# untitled.net
KiCad netlist of a schematic drawn in EAGLE
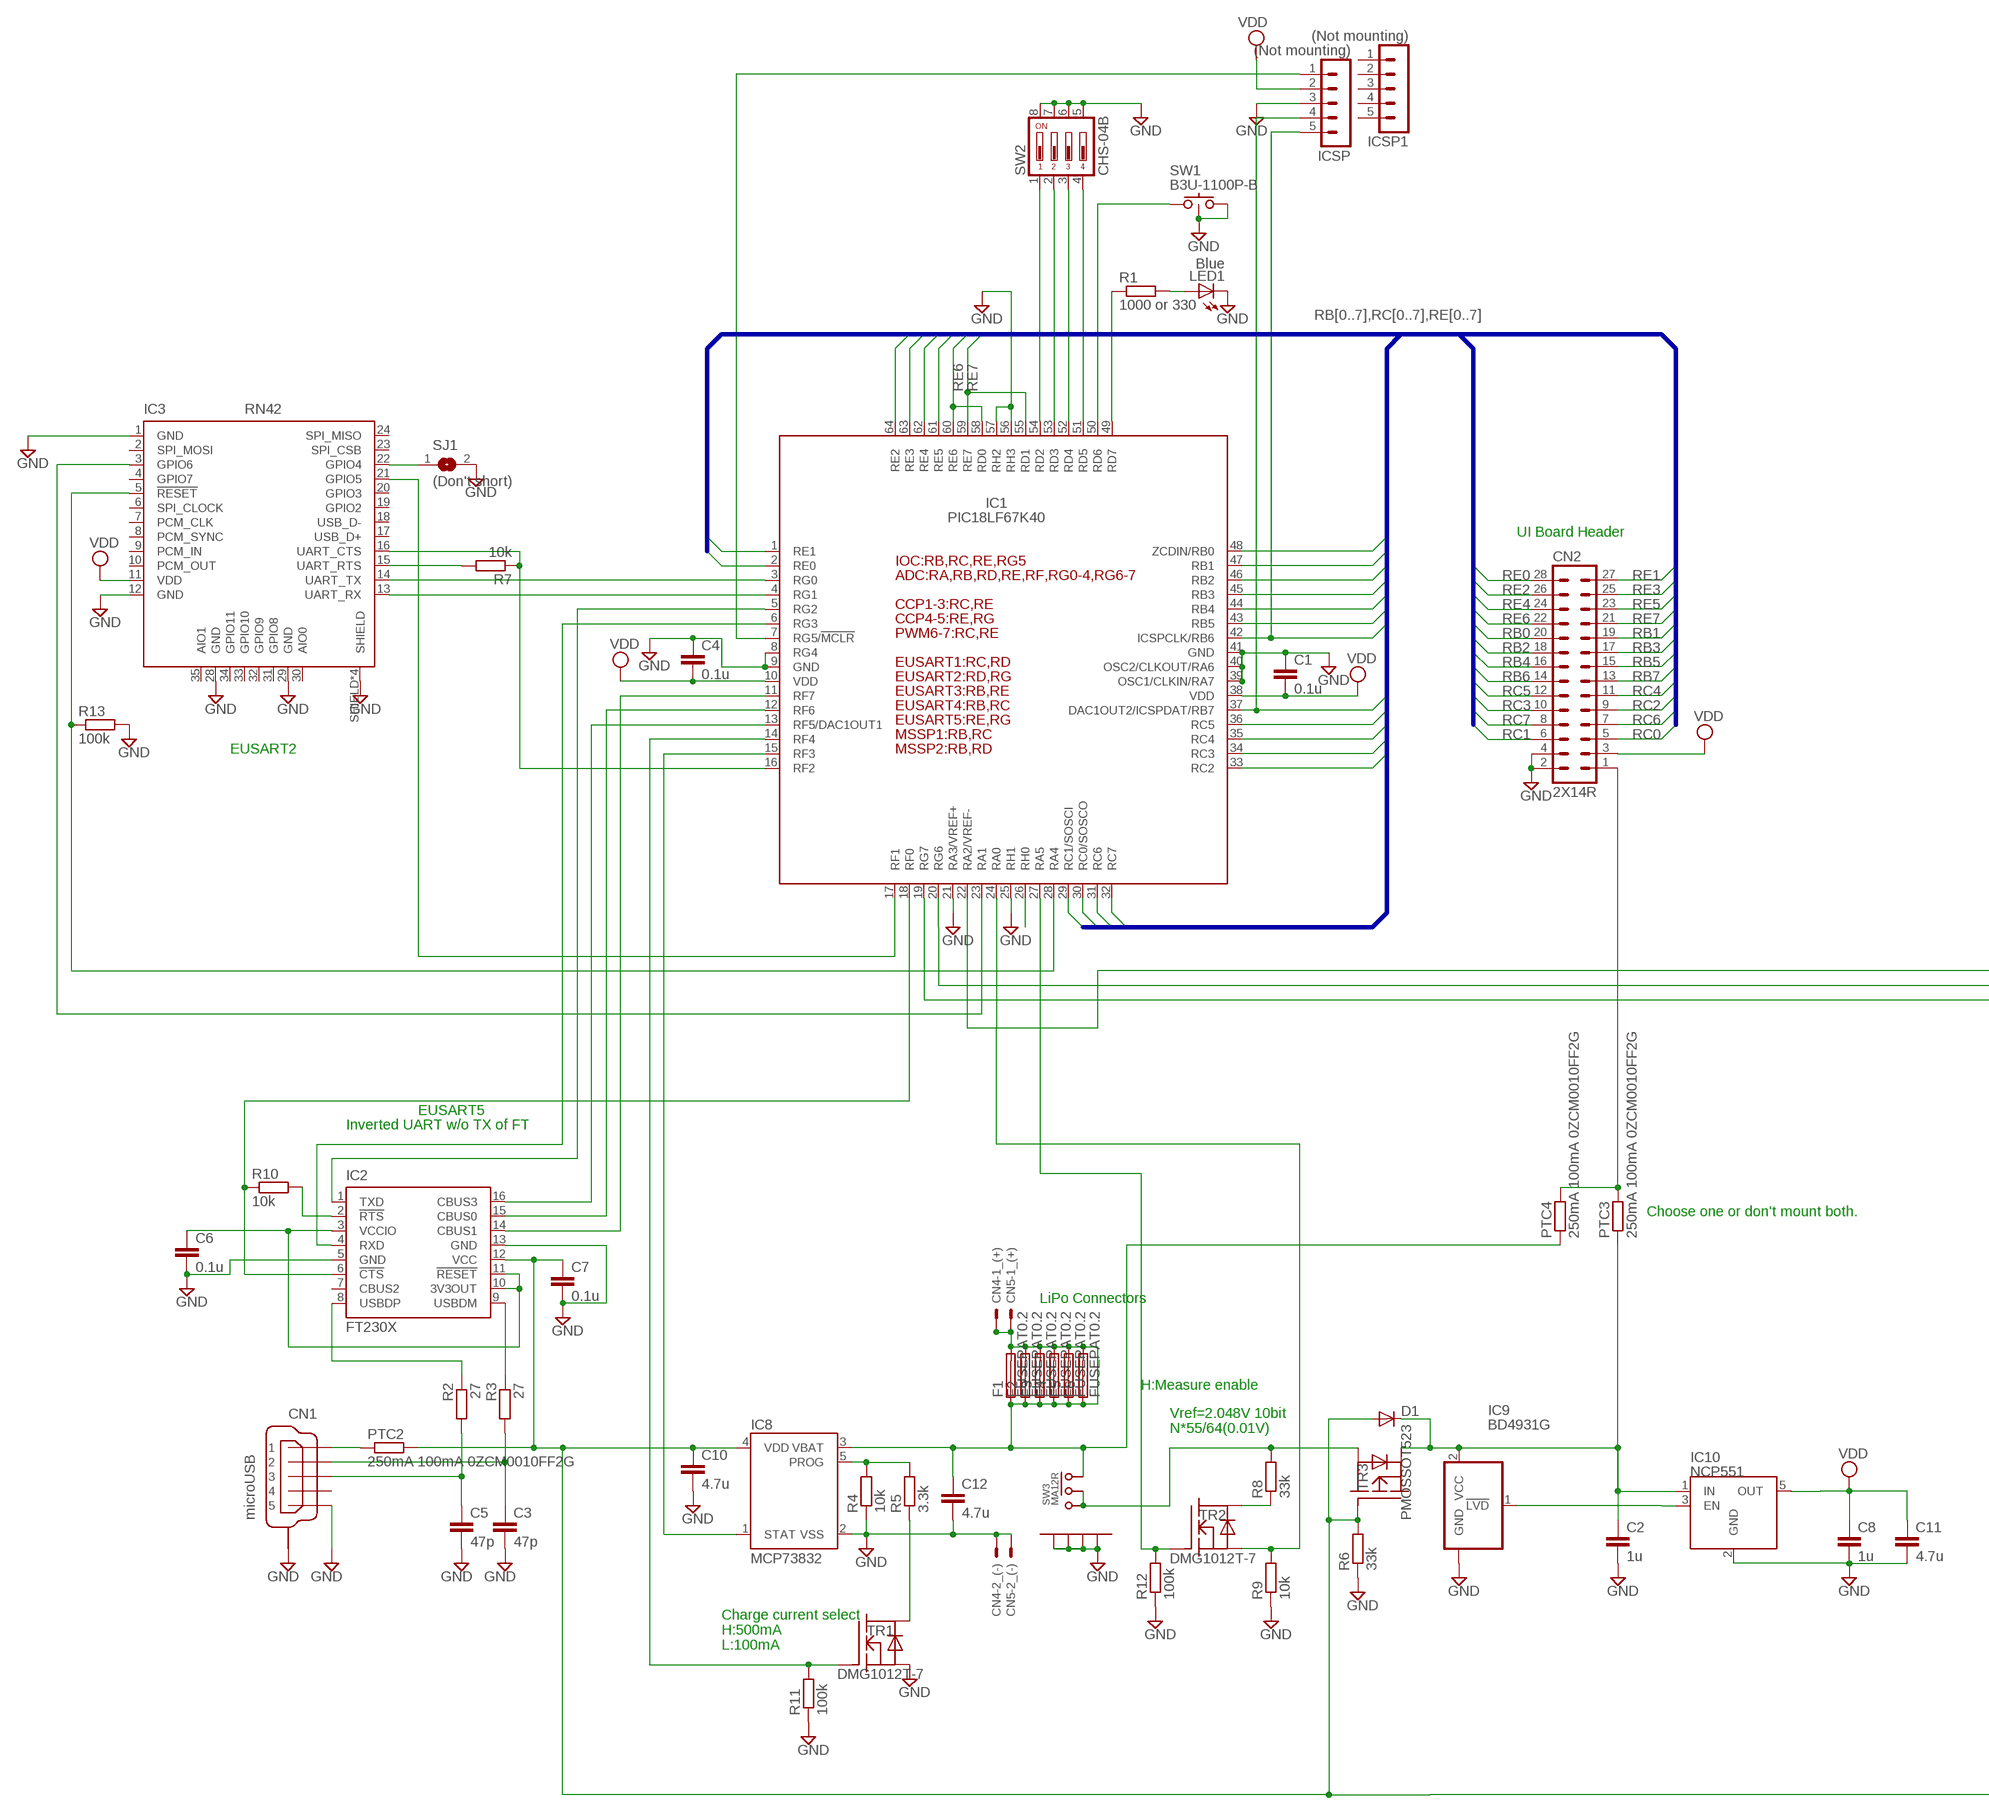
[diagram p0: schematic, sheet 1, part 1 of 2]
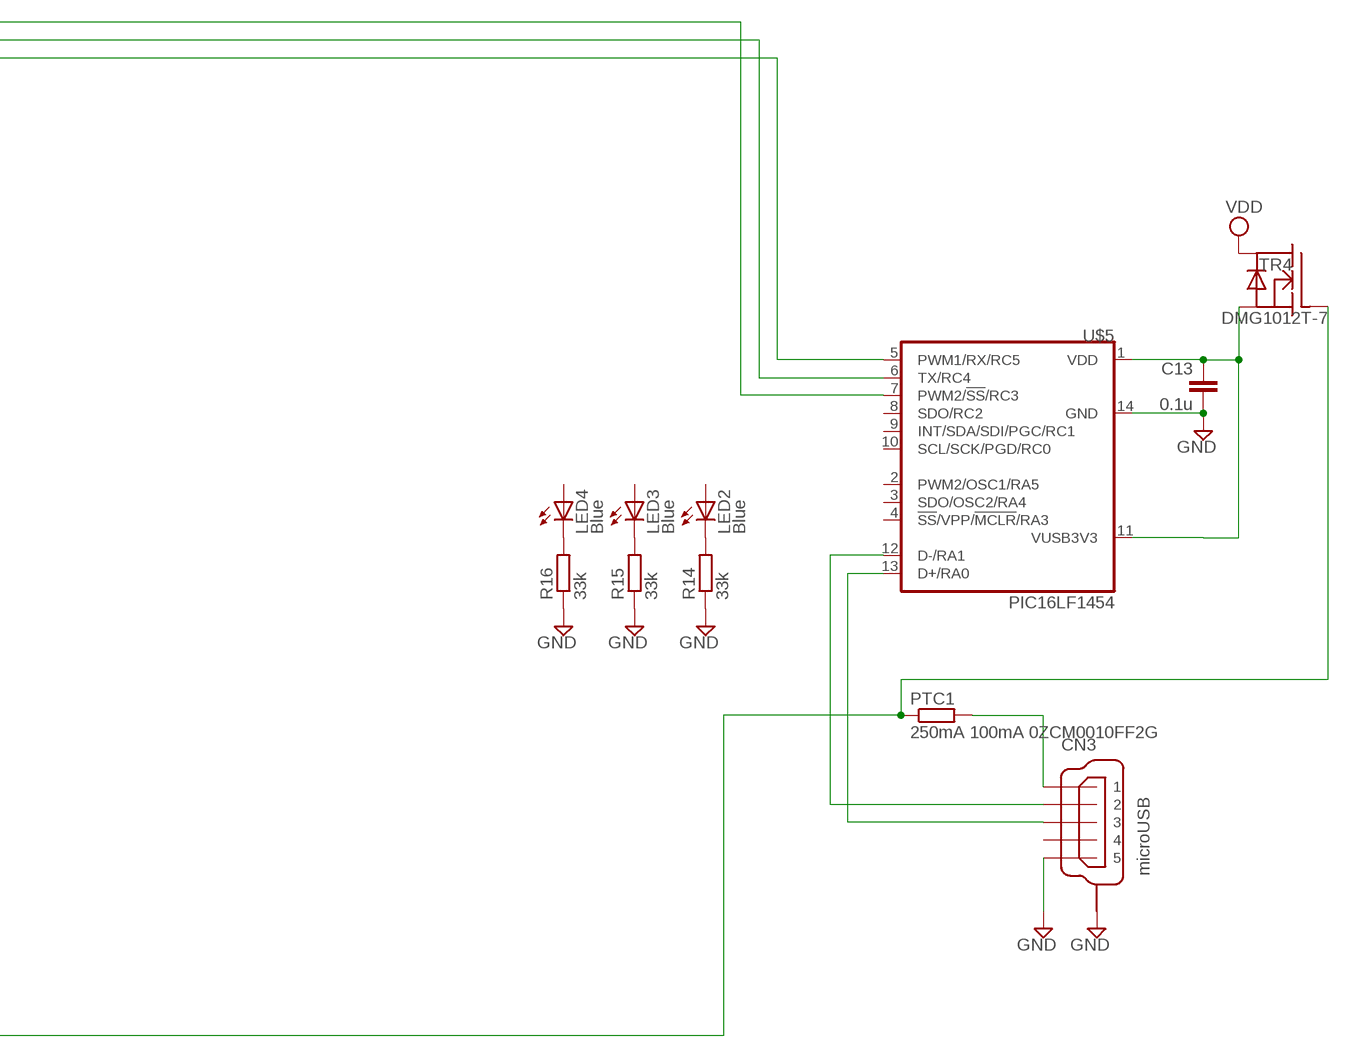
[diagram p1: schematic, sheet 1, part 2 of 2]

(export (version "E")
  (design (tool "Eeschema 10.0.6"))
  (components
    (comp (ref "C1")
      (value "0.1u")
      (footprint "eagle-import:C0402-SS")
      (libsource (lib "eagle-import") (part "C-EUC0402-SS"))
    )
    (comp (ref "C2")
      (value "1u")
      (footprint "eagle-import:C0805")
      (libsource (lib "eagle-import") (part "C-EUC0805"))
    )
    (comp (ref "C3")
      (value "47p")
      (footprint "eagle-import:C0402-SS")
      (libsource (lib "eagle-import") (part "C-EUC0402-SS"))
    )
    (comp (ref "C4")
      (value "0.1u")
      (footprint "eagle-import:C0402-SS")
      (libsource (lib "eagle-import") (part "C-EUC0402-SS"))
    )
    (comp (ref "C5")
      (value "47p")
      (footprint "eagle-import:C0402-SS")
      (libsource (lib "eagle-import") (part "C-EUC0402-SS"))
    )
    (comp (ref "C6")
      (value "0.1u")
      (footprint "eagle-import:C0402-SS")
      (libsource (lib "eagle-import") (part "C-EUC0402-SS"))
    )
    (comp (ref "C7")
      (value "0.1u")
      (footprint "eagle-import:C0402-SS")
      (libsource (lib "eagle-import") (part "C-EUC0402-SS"))
    )
    (comp (ref "C8")
      (value "1u")
      (footprint "eagle-import:C0805")
      (libsource (lib "eagle-import") (part "C-EUC0805"))
    )
    (comp (ref "C10")
      (value "4.7u")
      (footprint "eagle-import:C0805")
      (libsource (lib "eagle-import") (part "C-EUC0805"))
    )
    (comp (ref "C11")
      (value "4.7u")
      (footprint "eagle-import:C0805")
      (libsource (lib "eagle-import") (part "C-EUC0805"))
    )
    (comp (ref "C12")
      (value "4.7u")
      (footprint "eagle-import:C0805")
      (libsource (lib "eagle-import") (part "C-EUC0805"))
    )
    (comp (ref "C13")
      (value "0.1u")
      (footprint "eagle-import:C0402-SS")
      (libsource (lib "eagle-import") (part "C-EUC0402-SS"))
    )
    (comp (ref "CN1")
      (value "microUSB")
      (footprint "eagle-import:10118194-0001LF")
      (libsource (lib "eagle-import") (part "MICROUSB(10118194-0001LF)"))
    )
    (comp (ref "CN2")
      (value "2X14R")
      (footprint "eagle-import:2MM_14X2_R")
      (libsource (lib "eagle-import") (part "2X14R"))
    )
    (comp (ref "CN3")
      (value "microUSB")
      (footprint "eagle-import:10118194-0001LF")
      (libsource (lib "eagle-import") (part "MICROUSB(10118194-0001LF)"))
    )
    (comp (ref "CN4")
      (value "2P_(POWER)PH_S")
      (footprint "eagle-import:PH-2_S")
      (libsource (lib "eagle-import") (part "2P_(POWER)PH_S"))
    )
    (comp (ref "CN5")
      (value "2P_(POWER)PH_S")
      (footprint "eagle-import:PH-2_S")
      (libsource (lib "eagle-import") (part "2P_(POWER)PH_S"))
    )
    (comp (ref "D1")
      (value "DIODE-VMN2")
      (footprint "eagle-import:VMN2")
      (libsource (lib "eagle-import") (part "DIODE-VMN2"))
    )
    (comp (ref "F1")
      (value "FUSEPAT0.2")
      (footprint "eagle-import:FUSE_PAT1")
      (libsource (lib "eagle-import") (part "FUSEPAT0.2"))
    )
    (comp (ref "F2")
      (value "FUSEPAT0.2")
      (footprint "eagle-import:FUSE_PAT1")
      (libsource (lib "eagle-import") (part "FUSEPAT0.2"))
    )
    (comp (ref "F3")
      (value "FUSEPAT0.2")
      (footprint "eagle-import:FUSE_PAT1")
      (libsource (lib "eagle-import") (part "FUSEPAT0.2"))
    )
    (comp (ref "F4")
      (value "FUSEPAT0.2")
      (footprint "eagle-import:FUSE_PAT1")
      (libsource (lib "eagle-import") (part "FUSEPAT0.2"))
    )
    (comp (ref "F5")
      (value "FUSEPAT0.2")
      (footprint "eagle-import:FUSE_PAT1")
      (libsource (lib "eagle-import") (part "FUSEPAT0.2"))
    )
    (comp (ref "F6")
      (value "FUSEPAT0.2")
      (footprint "eagle-import:FUSE_PAT1")
      (libsource (lib "eagle-import") (part "FUSEPAT0.2"))
    )
    (comp (ref "IC1")
      (value "PIC18LF67K40")
      (footprint "eagle-import:TQFP64-10X10")
      (libsource (lib "eagle-import") (part "PIC18F67K40"))
    )
    (comp (ref "IC2")
      (value "FT230X")
      (footprint "eagle-import:SSOP16")
      (libsource (lib "eagle-import") (part "FT230XS"))
    )
    (comp (ref "IC3")
      (value "RN42")
      (footprint "eagle-import:RN-42")
      (libsource (lib "eagle-import") (part "RN-42"))
    )
    (comp (ref "IC8")
      (value "MCP73832")
      (footprint "eagle-import:SOT23-5L")
      (libsource (lib "eagle-import") (part "MCP73831"))
    )
    (comp (ref "IC9")
      (value "BD4931G")
      (footprint "eagle-import:SOT23-5L")
      (libsource (lib "eagle-import") (part "BD48XX"))
    )
    (comp (ref "IC10")
      (value "NCP551")
      (footprint "eagle-import:SOT23-5L")
      (libsource (lib "eagle-import") (part "NCP551"))
    )
    (comp (ref "ICSP")
      (value "(Not mounting)")
      (footprint "eagle-import:MA05-1")
      (libsource (lib "eagle-import") (part "MA05-1"))
    )
    (comp (ref "ICSP1")
      (value "(Not mounting)")
      (footprint "eagle-import:MA05-1")
      (libsource (lib "eagle-import") (part "MA05-1"))
    )
    (comp (ref "LED1")
      (value "Blue")
      (footprint "eagle-import:CHIP-LED1005")
      (libsource (lib "eagle-import") (part "LED1005"))
    )
    (comp (ref "LED2")
      (value "Blue")
      (footprint "eagle-import:CHIP-LED1606(SIDE)")
      (libsource (lib "eagle-import") (part "LEDCHIPLED_1606(SIDE)"))
    )
    (comp (ref "LED3")
      (value "Blue")
      (footprint "eagle-import:CHIP-LED1606(SIDE)")
      (libsource (lib "eagle-import") (part "LEDCHIPLED_1606(SIDE)"))
    )
    (comp (ref "LED4")
      (value "Blue")
      (footprint "eagle-import:CHIP-LED1606(SIDE)")
      (libsource (lib "eagle-import") (part "LEDCHIPLED_1606(SIDE)"))
    )
    (comp (ref "PTC1")
      (value "250mA 100mA 0ZCM0010FF2G")
      (footprint "eagle-import:R0603")
      (libsource (lib "eagle-import") (part "R-EU_R0603"))
    )
    (comp (ref "PTC2")
      (value "250mA 100mA 0ZCM0010FF2G")
      (footprint "eagle-import:R0603")
      (libsource (lib "eagle-import") (part "R-EU_R0603"))
    )
    (comp (ref "PTC3")
      (value "250mA 100mA 0ZCM0010FF2G")
      (footprint "eagle-import:R0603")
      (libsource (lib "eagle-import") (part "R-EU_R0603"))
    )
    (comp (ref "PTC4")
      (value "250mA 100mA 0ZCM0010FF2G")
      (footprint "eagle-import:R0603")
      (libsource (lib "eagle-import") (part "R-EU_R0603"))
    )
    (comp (ref "R1")
      (value "1000 or 330")
      (footprint "eagle-import:R0402-SS")
      (libsource (lib "eagle-import") (part "R-EU_R0402-SS"))
    )
    (comp (ref "R2")
      (value "27")
      (footprint "eagle-import:R0402-SS")
      (libsource (lib "eagle-import") (part "R-EU_R0402-SS"))
    )
    (comp (ref "R3")
      (value "27")
      (footprint "eagle-import:R0402-SS")
      (libsource (lib "eagle-import") (part "R-EU_R0402-SS"))
    )
    (comp (ref "R4")
      (value "10k")
      (footprint "eagle-import:R0402-SS")
      (libsource (lib "eagle-import") (part "R-EU_R0402-SS"))
    )
    (comp (ref "R5")
      (value "3.3k")
      (footprint "eagle-import:R0402-SS")
      (libsource (lib "eagle-import") (part "R-EU_R0402-SS"))
    )
    (comp (ref "R6")
      (value "33k")
      (footprint "eagle-import:R0402-SS")
      (libsource (lib "eagle-import") (part "R-EU_R0402-SS"))
    )
    (comp (ref "R7")
      (value "10k")
      (footprint "eagle-import:R0402-SS")
      (libsource (lib "eagle-import") (part "R-EU_R0402-SS"))
    )
    (comp (ref "R8")
      (value "33k")
      (footprint "eagle-import:R0402-SS")
      (libsource (lib "eagle-import") (part "R-EU_R0402-SS"))
    )
    (comp (ref "R9")
      (value "10k")
      (footprint "eagle-import:R0402-SS")
      (libsource (lib "eagle-import") (part "R-EU_R0402-SS"))
    )
    (comp (ref "R10")
      (value "10k")
      (footprint "eagle-import:R0402-SS")
      (libsource (lib "eagle-import") (part "R-EU_R0402-SS"))
    )
    (comp (ref "R11")
      (value "100k")
      (footprint "eagle-import:R0402-SS")
      (libsource (lib "eagle-import") (part "R-EU_R0402-SS"))
    )
    (comp (ref "R12")
      (value "100k")
      (footprint "eagle-import:R0402-SS")
      (libsource (lib "eagle-import") (part "R-EU_R0402-SS"))
    )
    (comp (ref "R13")
      (value "100k")
      (footprint "eagle-import:R0402-SS")
      (libsource (lib "eagle-import") (part "R-EU_R0402-SS"))
    )
    (comp (ref "R14")
      (value "33k")
      (footprint "eagle-import:R0402-SS")
      (libsource (lib "eagle-import") (part "R-EU_R0402-SS"))
    )
    (comp (ref "R15")
      (value "33k")
      (footprint "eagle-import:R0402-SS")
      (libsource (lib "eagle-import") (part "R-EU_R0402-SS"))
    )
    (comp (ref "R16")
      (value "33k")
      (footprint "eagle-import:R0402-SS")
      (libsource (lib "eagle-import") (part "R-EU_R0402-SS"))
    )
    (comp (ref "SJ1")
      (value "(Don't short)")
      (footprint "eagle-import:SJ")
      (libsource (lib "eagle-import") (part "SJ"))
    )
    (comp (ref "SW1")
      (value "B3U-1100P-B")
      (footprint "eagle-import:B3U-1100P-B")
      (libsource (lib "eagle-import") (part "SW_WITH_EARTH(B3U-1100P)"))
    )
    (comp (ref "SW2")
      (value "CHS-04B")
      (footprint "eagle-import:CHS-04B")
      (libsource (lib "eagle-import") (part "CHS-04B"))
    )
    (comp (ref "SW3")
      (value "MA12R")
      (footprint "eagle-import:MA12R")
      (libsource (lib "eagle-import") (part "MA12R"))
    )
    (comp (ref "TR1")
      (value "DMG1012T-7")
      (footprint "eagle-import:SOT523")
      (libsource (lib "eagle-import") (part "NMOSSOT523"))
    )
    (comp (ref "TR2")
      (value "DMG1012T-7")
      (footprint "eagle-import:SOT523")
      (libsource (lib "eagle-import") (part "NMOSSOT523"))
    )
    (comp (ref "TR3")
      (value "PMOSSOT523")
      (footprint "eagle-import:SOT523")
      (libsource (lib "eagle-import") (part "PMOSSOT523"))
    )
    (comp (ref "TR4")
      (value "DMG1012T-7")
      (footprint "eagle-import:SOT523")
      (libsource (lib "eagle-import") (part "NMOSSOT523"))
    )
    (comp (ref "U$5")
      (value "PIC16LF1454")
      (footprint "eagle-import:TSSOP14")
      (libsource (lib "eagle-import") (part "PIC16F1454"))
    )
  )
  (nets
    (net (code "1") (name "/RB0") (class "Default")
      (node (ref "CN2") (pin "20") (pinfunction "20_20") (pintype "passive"))
      (node (ref "IC1") (pin "48") (pinfunction "ZCDIN/RB0_48") (pintype "bidirectional"))
    )
    (net (code "2") (name "/RB1") (class "Default")
      (node (ref "CN2") (pin "19") (pinfunction "19_19") (pintype "passive"))
      (node (ref "IC1") (pin "47") (pinfunction "RB1_47") (pintype "bidirectional"))
    )
    (net (code "3") (name "/RB2") (class "Default")
      (node (ref "CN2") (pin "18") (pinfunction "18_18") (pintype "passive"))
      (node (ref "IC1") (pin "46") (pinfunction "RB2_46") (pintype "bidirectional"))
    )
    (net (code "4") (name "/RB3") (class "Default")
      (node (ref "CN2") (pin "17") (pinfunction "17_17") (pintype "passive"))
      (node (ref "IC1") (pin "45") (pinfunction "RB3_45") (pintype "bidirectional"))
    )
    (net (code "5") (name "/RB4") (class "Default")
      (node (ref "CN2") (pin "16") (pinfunction "16_16") (pintype "passive"))
      (node (ref "IC1") (pin "44") (pinfunction "RB4_44") (pintype "bidirectional"))
    )
    (net (code "6") (name "/RB5") (class "Default")
      (node (ref "CN2") (pin "15") (pinfunction "15_15") (pintype "passive"))
      (node (ref "IC1") (pin "43") (pinfunction "RB5_43") (pintype "bidirectional"))
    )
    (net (code "7") (name "/RB6") (class "Default")
      (node (ref "CN2") (pin "14") (pinfunction "14_14") (pintype "passive"))
      (node (ref "IC1") (pin "42") (pinfunction "ICSPCLK/RB6_42") (pintype "bidirectional"))
      (node (ref "ICSP") (pin "5") (pinfunction "5_5") (pintype "passive"))
    )
    (net (code "8") (name "/RB7") (class "Default")
      (node (ref "CN2") (pin "13") (pinfunction "13_13") (pintype "passive"))
      (node (ref "IC1") (pin "37") (pinfunction "DAC1OUT2/ICSPDAT/RB7_37") (pintype "bidirectional"))
      (node (ref "ICSP") (pin "4") (pinfunction "4_4") (pintype "passive"))
    )
    (net (code "9") (name "/RC0") (class "Default")
      (node (ref "CN2") (pin "5") (pinfunction "5_5") (pintype "passive"))
      (node (ref "IC1") (pin "30") (pinfunction "RC0/SOSCO_30") (pintype "bidirectional"))
    )
    (net (code "10") (name "/RC1") (class "Default")
      (node (ref "CN2") (pin "6") (pinfunction "6_6") (pintype "passive"))
      (node (ref "IC1") (pin "29") (pinfunction "RC1/SOSCI_29") (pintype "bidirectional"))
    )
    (net (code "11") (name "/RC2") (class "Default")
      (node (ref "CN2") (pin "9") (pinfunction "9_9") (pintype "passive"))
      (node (ref "IC1") (pin "33") (pinfunction "RC2_33") (pintype "bidirectional"))
    )
    (net (code "12") (name "/RC3") (class "Default")
      (node (ref "CN2") (pin "10") (pinfunction "10_10") (pintype "passive"))
      (node (ref "IC1") (pin "34") (pinfunction "RC3_34") (pintype "bidirectional"))
    )
    (net (code "13") (name "/RC4") (class "Default")
      (node (ref "CN2") (pin "11") (pinfunction "11_11") (pintype "passive"))
      (node (ref "IC1") (pin "35") (pinfunction "RC4_35") (pintype "bidirectional"))
    )
    (net (code "14") (name "/RC5") (class "Default")
      (node (ref "CN2") (pin "12") (pinfunction "12_12") (pintype "passive"))
      (node (ref "IC1") (pin "36") (pinfunction "RC5_36") (pintype "bidirectional"))
    )
    (net (code "15") (name "/RC6") (class "Default")
      (node (ref "CN2") (pin "7") (pinfunction "7_7") (pintype "passive"))
      (node (ref "IC1") (pin "31") (pinfunction "RC6_31") (pintype "bidirectional"))
    )
    (net (code "16") (name "/RC7") (class "Default")
      (node (ref "CN2") (pin "8") (pinfunction "8_8") (pintype "passive"))
      (node (ref "IC1") (pin "32") (pinfunction "RC7_32") (pintype "bidirectional"))
    )
    (net (code "17") (name "/RE0") (class "Default")
      (node (ref "CN2") (pin "28") (pinfunction "28_28") (pintype "passive"))
      (node (ref "IC1") (pin "2") (pinfunction "RE0_2") (pintype "bidirectional"))
    )
    (net (code "18") (name "/RE1") (class "Default")
      (node (ref "CN2") (pin "27") (pinfunction "27_27") (pintype "passive"))
      (node (ref "IC1") (pin "1") (pinfunction "RE1_1") (pintype "bidirectional"))
    )
    (net (code "19") (name "/RE2") (class "Default")
      (node (ref "CN2") (pin "26") (pinfunction "26_26") (pintype "passive"))
      (node (ref "IC1") (pin "64") (pinfunction "RE2_64") (pintype "bidirectional"))
    )
    (net (code "20") (name "/RE3") (class "Default")
      (node (ref "CN2") (pin "25") (pinfunction "25_25") (pintype "passive"))
      (node (ref "IC1") (pin "63") (pinfunction "RE3_63") (pintype "bidirectional"))
    )
    (net (code "21") (name "/RE4") (class "Default")
      (node (ref "CN2") (pin "24") (pinfunction "24_24") (pintype "passive"))
      (node (ref "IC1") (pin "62") (pinfunction "RE4_62") (pintype "bidirectional"))
    )
    (net (code "22") (name "/RE5") (class "Default")
      (node (ref "CN2") (pin "23") (pinfunction "23_23") (pintype "passive"))
      (node (ref "IC1") (pin "61") (pinfunction "RE5_61") (pintype "bidirectional"))
    )
    (net (code "23") (name "/RE6") (class "Default")
      (node (ref "CN2") (pin "22") (pinfunction "22_22") (pintype "passive"))
      (node (ref "IC1") (pin "58") (pinfunction "RD0_58") (pintype "bidirectional"))
      (node (ref "IC1") (pin "60") (pinfunction "RE6_60") (pintype "bidirectional"))
    )
    (net (code "24") (name "/RE7") (class "Default")
      (node (ref "CN2") (pin "21") (pinfunction "21_21") (pintype "passive"))
      (node (ref "IC1") (pin "55") (pinfunction "RD1_55") (pintype "bidirectional"))
      (node (ref "IC1") (pin "59") (pinfunction "RE7_59") (pintype "bidirectional"))
    )
    (net (code "26") (name "GND") (class "Default")
      (node (ref "C1") (pin "1") (pinfunction "1_1") (pintype "passive"))
      (node (ref "C10") (pin "2") (pinfunction "2_2") (pintype "passive"))
      (node (ref "C11") (pin "2") (pinfunction "2_2") (pintype "passive"))
      (node (ref "C12") (pin "2") (pinfunction "2_2") (pintype "passive"))
      (node (ref "C13") (pin "2") (pinfunction "2_2") (pintype "passive"))
      (node (ref "C2") (pin "2") (pinfunction "2_2") (pintype "passive"))
      (node (ref "C3") (pin "2") (pinfunction "2_2") (pintype "passive"))
      (node (ref "C4") (pin "1") (pinfunction "1_1") (pintype "passive"))
      (node (ref "C5") (pin "2") (pinfunction "2_2") (pintype "passive"))
      (node (ref "C6") (pin "2") (pinfunction "2_2") (pintype "passive"))
      (node (ref "C7") (pin "2") (pinfunction "2_2") (pintype "passive"))
      (node (ref "C8") (pin "2") (pinfunction "2_2") (pintype "passive"))
      (node (ref "CN1") (pin "P$5") (pinfunction "5_P$5") (pintype "passive"))
      (node (ref "CN1") (pin "P$6") (pinfunction "S_P$6") (pintype "passive"))
      (node (ref "CN1") (pin "P$7") (pinfunction "S_P$7") (pintype "passive"))
      (node (ref "CN1") (pin "S1") (pinfunction "S_S1") (pintype "passive"))
      (node (ref "CN1") (pin "S10") (pinfunction "S_S10") (pintype "passive"))
      (node (ref "CN1") (pin "S2") (pinfunction "S_S2") (pintype "passive"))
      (node (ref "CN1") (pin "S3") (pinfunction "S_S3") (pintype "passive"))
      (node (ref "CN1") (pin "S4") (pinfunction "S_S4") (pintype "passive"))
      (node (ref "CN1") (pin "S5") (pinfunction "S_S5") (pintype "passive"))
      (node (ref "CN1") (pin "S6") (pinfunction "S_S6") (pintype "passive"))
      (node (ref "CN1") (pin "S7") (pinfunction "S_S7") (pintype "passive"))
      (node (ref "CN1") (pin "S8") (pinfunction "S_S8") (pintype "passive"))
      (node (ref "CN1") (pin "S9") (pinfunction "S_S9") (pintype "passive"))
      (node (ref "CN2") (pin "2") (pinfunction "2_2") (pintype "passive"))
      (node (ref "CN2") (pin "4") (pinfunction "4_4") (pintype "passive"))
      (node (ref "CN3") (pin "P$5") (pinfunction "5_P$5") (pintype "passive"))
      (node (ref "CN3") (pin "P$6") (pinfunction "S_P$6") (pintype "passive"))
      (node (ref "CN3") (pin "P$7") (pinfunction "S_P$7") (pintype "passive"))
      (node (ref "CN3") (pin "S1") (pinfunction "S_S1") (pintype "passive"))
      (node (ref "CN3") (pin "S10") (pinfunction "S_S10") (pintype "passive"))
      (node (ref "CN3") (pin "S2") (pinfunction "S_S2") (pintype "passive"))
      (node (ref "CN3") (pin "S3") (pinfunction "S_S3") (pintype "passive"))
      (node (ref "CN3") (pin "S4") (pinfunction "S_S4") (pintype "passive"))
      (node (ref "CN3") (pin "S5") (pinfunction "S_S5") (pintype "passive"))
      (node (ref "CN3") (pin "S6") (pinfunction "S_S6") (pintype "passive"))
      (node (ref "CN3") (pin "S7") (pinfunction "S_S7") (pintype "passive"))
      (node (ref "CN3") (pin "S8") (pinfunction "S_S8") (pintype "passive"))
      (node (ref "CN3") (pin "S9") (pinfunction "S_S9") (pintype "passive"))
      (node (ref "CN4") (pin "2") (pinfunction "S_2") (pintype "passive"))
      (node (ref "CN5") (pin "2") (pinfunction "S_2") (pintype "passive"))
      (node (ref "IC1") (pin "21") (pinfunction "RA3/VREF+_21") (pintype "bidirectional"))
      (node (ref "IC1") (pin "25") (pinfunction "RH1_25") (pintype "bidirectional"))
      (node (ref "IC1") (pin "39") (pinfunction "OSC1/CLKIN/RA7_39") (pintype "bidirectional"))
      (node (ref "IC1") (pin "40") (pinfunction "OSC2/CLKOUT/RA6_40") (pintype "bidirectional"))
      (node (ref "IC1") (pin "41") (pinfunction "GND_41") (pintype "power_in"))
      (node (ref "IC1") (pin "56") (pinfunction "RH3_56") (pintype "bidirectional"))
      (node (ref "IC1") (pin "57") (pinfunction "RH2_57") (pintype "bidirectional"))
      (node (ref "IC1") (pin "8") (pinfunction "RG4_8") (pintype "bidirectional"))
      (node (ref "IC1") (pin "9") (pinfunction "GND_9") (pintype "power_in"))
      (node (ref "IC10") (pin "2") (pinfunction "GND_2") (pintype "power_in"))
      (node (ref "IC2") (pin "13") (pinfunction "GND_13") (pintype "power_in"))
      (node (ref "IC2") (pin "5") (pinfunction "GND_5") (pintype "power_in"))
      (node (ref "IC3") (pin "1") (pinfunction "GND_1") (pintype "bidirectional"))
      (node (ref "IC3") (pin "12") (pinfunction "GND_12") (pintype "bidirectional"))
      (node (ref "IC3") (pin "28") (pinfunction "GND_28") (pintype "bidirectional"))
      (node (ref "IC3") (pin "29") (pinfunction "GND_29") (pintype "bidirectional"))
      (node (ref "IC3") (pin "SHIELD") (pinfunction "SHIELD_SHIELD") (pintype "bidirectional"))
      (node (ref "IC3") (pin "SHIELD@1") (pinfunction "SHIELD_SHIELD@1") (pintype "bidirectional"))
      (node (ref "IC3") (pin "SHIELD@2") (pinfunction "SHIELD_SHIELD@2") (pintype "bidirectional"))
      (node (ref "IC3") (pin "SHIELD@3") (pinfunction "SHIELD_SHIELD@3") (pintype "bidirectional"))
      (node (ref "IC8") (pin "2") (pinfunction "VSS_2") (pintype "power_in"))
      (node (ref "IC9") (pin "3") (pinfunction "GND_3") (pintype "power_in"))
      (node (ref "ICSP") (pin "3") (pinfunction "3_3") (pintype "passive"))
      (node (ref "LED1") (pin "C") (pinfunction "C_C") (pintype "passive"))
      (node (ref "R11") (pin "1") (pinfunction "1_1") (pintype "passive"))
      (node (ref "R12") (pin "1") (pinfunction "1_1") (pintype "passive"))
      (node (ref "R13") (pin "2") (pinfunction "2_2") (pintype "passive"))
      (node (ref "R14") (pin "1") (pinfunction "1_1") (pintype "passive"))
      (node (ref "R15") (pin "1") (pinfunction "1_1") (pintype "passive"))
      (node (ref "R16") (pin "1") (pinfunction "1_1") (pintype "passive"))
      (node (ref "R4") (pin "1") (pinfunction "1_1") (pintype "passive"))
      (node (ref "R6") (pin "1") (pinfunction "1_1") (pintype "passive"))
      (node (ref "R9") (pin "1") (pinfunction "1_1") (pintype "passive"))
      (node (ref "SJ1") (pin "2") (pinfunction "2_2") (pintype "passive"))
      (node (ref "SW1") (pin "P$2") (pinfunction "P$2_P$2") (pintype "passive"))
      (node (ref "SW1") (pin "P$3") (pinfunction "P$3_P$3") (pintype "passive"))
      (node (ref "SW2") (pin "5") (pinfunction "5_5") (pintype "passive"))
      (node (ref "SW2") (pin "6") (pinfunction "6_6") (pintype "passive"))
      (node (ref "SW2") (pin "7") (pinfunction "7_7") (pintype "passive"))
      (node (ref "SW2") (pin "8") (pinfunction "8_8") (pintype "passive"))
      (node (ref "SW3") (pin "P$4") (pinfunction "P$1_P$4") (pintype "bidirectional"))
      (node (ref "SW3") (pin "P$5") (pinfunction "P$2_P$5") (pintype "bidirectional"))
      (node (ref "SW3") (pin "P$6") (pinfunction "P$3_P$6") (pintype "bidirectional"))
      (node (ref "SW3") (pin "P$7") (pinfunction "P$4_P$7") (pintype "bidirectional"))
      (node (ref "TR1") (pin "2") (pinfunction "S_2") (pintype "bidirectional"))
      (node (ref "U$5") (pin "14") (pinfunction "GND_14") (pintype "power_in"))
    )
    (net (code "27") (name "Net-(CN1-1)") (class "Default")
      (node (ref "CN1") (pin "P$1") (pinfunction "1_P$1") (pintype "passive"))
      (node (ref "PTC2") (pin "1") (pinfunction "1_1") (pintype "passive"))
    )
    (net (code "28") (name "Net-(CN1-2)") (class "Default")
      (node (ref "C3") (pin "1") (pinfunction "1_1") (pintype "passive"))
      (node (ref "CN1") (pin "P$2") (pinfunction "2_P$2") (pintype "passive"))
      (node (ref "R3") (pin "2") (pinfunction "2_2") (pintype "passive"))
    )
    (net (code "29") (name "Net-(CN1-3)") (class "Default")
      (node (ref "C5") (pin "1") (pinfunction "1_1") (pintype "passive"))
      (node (ref "CN1") (pin "P$3") (pinfunction "3_P$3") (pintype "passive"))
      (node (ref "R2") (pin "2") (pinfunction "2_2") (pintype "passive"))
    )
    (net (code "30") (name "Net-(CN2-Pad1)") (class "Default")
      (node (ref "CN2") (pin "1") (pinfunction "1_1") (pintype "passive"))
      (node (ref "PTC3") (pin "2") (pinfunction "2_2") (pintype "passive"))
      (node (ref "PTC4") (pin "2") (pinfunction "2_2") (pintype "passive"))
    )
    (net (code "31") (name "Net-(CN3-1)") (class "Default")
      (node (ref "CN3") (pin "P$1") (pinfunction "1_P$1") (pintype "passive"))
      (node (ref "PTC1") (pin "2") (pinfunction "2_2") (pintype "passive"))
    )
    (net (code "32") (name "Net-(CN3-2)") (class "Default")
      (node (ref "CN3") (pin "P$2") (pinfunction "2_P$2") (pintype "passive"))
      (node (ref "U$5") (pin "12") (pinfunction "D-/RA1_12") (pintype "bidirectional"))
    )
    (net (code "33") (name "Net-(CN3-3)") (class "Default")
      (node (ref "CN3") (pin "P$3") (pinfunction "3_P$3") (pintype "passive"))
      (node (ref "U$5") (pin "13") (pinfunction "D+/RA0_13") (pintype "bidirectional"))
    )
    (net (code "34") (name "Net-(CN4A-S)") (class "Default")
      (node (ref "C12") (pin "1") (pinfunction "1_1") (pintype "passive"))
      (node (ref "CN4") (pin "1") (pinfunction "S_1") (pintype "passive"))
      (node (ref "CN5") (pin "1") (pinfunction "S_1") (pintype "passive"))
      (node (ref "F1") (pin "P$1") (pinfunction "1_P$1") (pintype "passive"))
      (node (ref "F1") (pin "P$2") (pinfunction "2_P$2") (pintype "passive"))
      (node (ref "F2") (pin "P$1") (pinfunction "1_P$1") (pintype "passive"))
      (node (ref "F2") (pin "P$2") (pinfunction "2_P$2") (pintype "passive"))
      (node (ref "F3") (pin "P$1") (pinfunction "1_P$1") (pintype "passive"))
      (node (ref "F3") (pin "P$2") (pinfunction "2_P$2") (pintype "passive"))
      (node (ref "F4") (pin "P$1") (pinfunction "1_P$1") (pintype "passive"))
      (node (ref "F4") (pin "P$2") (pinfunction "2_P$2") (pintype "passive"))
      (node (ref "F5") (pin "P$1") (pinfunction "1_P$1") (pintype "passive"))
      (node (ref "F5") (pin "P$2") (pinfunction "2_P$2") (pintype "passive"))
      (node (ref "F6") (pin "P$1") (pinfunction "1_P$1") (pintype "passive"))
      (node (ref "F6") (pin "P$2") (pinfunction "2_P$2") (pintype "passive"))
      (node (ref "IC8") (pin "3") (pinfunction "VBAT_3") (pintype "output"))
      (node (ref "PTC4") (pin "1") (pinfunction "1_1") (pintype "passive"))
      (node (ref "SW3") (pin "P$1") (pinfunction "1_P$1") (pintype "bidirectional"))
    )
    (net (code "35") (name "Net-(IC1-RA0)") (class "Default")
      (node (ref "IC1") (pin "24") (pinfunction "RA0_24") (pintype "bidirectional"))
      (node (ref "R9") (pin "2") (pinfunction "2_2") (pintype "passive"))
      (node (ref "TR2") (pin "2") (pinfunction "S_2") (pintype "bidirectional"))
    )
    (net (code "36") (name "Net-(IC1-RA1)") (class "Default")
      (node (ref "IC1") (pin "23") (pinfunction "RA1_23") (pintype "bidirectional"))
      (node (ref "IC3") (pin "3") (pinfunction "GPIO6_3") (pintype "bidirectional"))
    )
    (net (code "37") (name "Net-(IC1-RA2{slash}VREF-)") (class "Default")
      (node (ref "IC1") (pin "22") (pinfunction "RA2/VREF-_22") (pintype "bidirectional"))
      (node (ref "U$5") (pin "7") (pinfunction "PWM2/~{SS}/RC3_7") (pintype "bidirectional"))
    )
    (net (code "38") (name "Net-(IC1-RA4)") (class "Default")
      (node (ref "IC1") (pin "28") (pinfunction "RA4_28") (pintype "bidirectional"))
      (node (ref "IC3") (pin "5") (pinfunction "~{RESET}_5") (pintype "bidirectional"))
      (node (ref "R13") (pin "1") (pinfunction "1_1") (pintype "passive"))
    )
    (net (code "39") (name "Net-(IC1-RA5)") (class "Default")
      (node (ref "IC1") (pin "27") (pinfunction "RA5_27") (pintype "bidirectional"))
      (node (ref "R12") (pin "2") (pinfunction "2_2") (pintype "passive"))
      (node (ref "TR2") (pin "1") (pinfunction "G_1") (pintype "bidirectional"))
    )
    (net (code "40") (name "Net-(IC1-RD2)") (class "Default")
      (node (ref "IC1") (pin "54") (pinfunction "RD2_54") (pintype "bidirectional"))
      (node (ref "SW2") (pin "1") (pinfunction "1_1") (pintype "passive"))
    )
    (net (code "41") (name "Net-(IC1-RD3)") (class "Default")
      (node (ref "IC1") (pin "53") (pinfunction "RD3_53") (pintype "bidirectional"))
      (node (ref "SW2") (pin "2") (pinfunction "2_2") (pintype "passive"))
    )
    (net (code "42") (name "Net-(IC1-RD4)") (class "Default")
      (node (ref "IC1") (pin "52") (pinfunction "RD4_52") (pintype "bidirectional"))
      (node (ref "SW2") (pin "3") (pinfunction "3_3") (pintype "passive"))
    )
    (net (code "43") (name "Net-(IC1-RD5)") (class "Default")
      (node (ref "IC1") (pin "51") (pinfunction "RD5_51") (pintype "bidirectional"))
      (node (ref "SW2") (pin "4") (pinfunction "4_4") (pintype "passive"))
    )
    (net (code "44") (name "Net-(IC1-RD6)") (class "Default")
      (node (ref "IC1") (pin "50") (pinfunction "RD6_50") (pintype "bidirectional"))
      (node (ref "SW1") (pin "P$1") (pinfunction "P$1_P$1") (pintype "passive"))
    )
    (net (code "45") (name "Net-(IC1-RD7)") (class "Default")
      (node (ref "IC1") (pin "49") (pinfunction "RD7_49") (pintype "bidirectional"))
      (node (ref "R1") (pin "1") (pinfunction "1_1") (pintype "passive"))
    )
    (net (code "46") (name "Net-(IC1-RF0)") (class "Default")
      (node (ref "IC1") (pin "18") (pinfunction "RF0_18") (pintype "bidirectional"))
      (node (ref "IC2") (pin "6") (pinfunction "~{CTS}_6") (pintype "input"))
      (node (ref "R10") (pin "1") (pinfunction "1_1") (pintype "passive"))
    )
    (net (code "47") (name "Net-(IC1-RF1)") (class "Default")
      (node (ref "IC1") (pin "17") (pinfunction "RF1_17") (pintype "bidirectional"))
      (node (ref "IC3") (pin "21") (pinfunction "GPIO5_21") (pintype "bidirectional"))
    )
    (net (code "48") (name "Net-(IC1-RF2)") (class "Default")
      (node (ref "IC1") (pin "16") (pinfunction "RF2_16") (pintype "bidirectional"))
      (node (ref "IC3") (pin "16") (pinfunction "UART_CTS_16") (pintype "bidirectional"))
      (node (ref "R7") (pin "1") (pinfunction "1_1") (pintype "passive"))
    )
    (net (code "49") (name "Net-(IC1-RF3)") (class "Default")
      (node (ref "IC1") (pin "15") (pinfunction "RF3_15") (pintype "bidirectional"))
      (node (ref "IC8") (pin "1") (pinfunction "STAT_1") (pintype "output"))
    )
    (net (code "50") (name "Net-(IC1-RF4)") (class "Default")
      (node (ref "IC1") (pin "14") (pinfunction "RF4_14") (pintype "bidirectional"))
      (node (ref "R11") (pin "2") (pinfunction "2_2") (pintype "passive"))
      (node (ref "TR1") (pin "1") (pinfunction "G_1") (pintype "bidirectional"))
    )
    (net (code "51") (name "Net-(IC1-RF5{slash}DAC1OUT1)") (class "Default")
      (node (ref "IC1") (pin "13") (pinfunction "RF5/DAC1OUT1_13") (pintype "bidirectional"))
      (node (ref "IC2") (pin "16") (pinfunction "CBUS3_16") (pintype "bidirectional"))
    )
    (net (code "52") (name "Net-(IC1-RF6)") (class "Default")
      (node (ref "IC1") (pin "12") (pinfunction "RF6_12") (pintype "bidirectional"))
      (node (ref "IC2") (pin "15") (pinfunction "CBUS0_15") (pintype "bidirectional"))
    )
    (net (code "53") (name "Net-(IC1-RF7)") (class "Default")
      (node (ref "IC1") (pin "11") (pinfunction "RF7_11") (pintype "bidirectional"))
      (node (ref "IC2") (pin "14") (pinfunction "CBUS1_14") (pintype "bidirectional"))
    )
    (net (code "54") (name "Net-(IC1-RG0)") (class "Default")
      (node (ref "IC1") (pin "3") (pinfunction "RG0_3") (pintype "bidirectional"))
      (node (ref "IC3") (pin "14") (pinfunction "UART_TX_14") (pintype "bidirectional"))
    )
    (net (code "55") (name "Net-(IC1-RG1)") (class "Default")
      (node (ref "IC1") (pin "4") (pinfunction "RG1_4") (pintype "bidirectional"))
      (node (ref "IC3") (pin "13") (pinfunction "UART_RX_13") (pintype "bidirectional"))
    )
    (net (code "56") (name "Net-(IC1-RG2)") (class "Default")
      (node (ref "IC1") (pin "5") (pinfunction "RG2_5") (pintype "bidirectional"))
      (node (ref "IC2") (pin "1") (pinfunction "TXD_1") (pintype "output"))
    )
    (net (code "57") (name "Net-(IC1-RG3)") (class "Default")
      (node (ref "IC1") (pin "6") (pinfunction "RG3_6") (pintype "bidirectional"))
      (node (ref "IC2") (pin "4") (pinfunction "RXD_4") (pintype "input"))
    )
    (net (code "58") (name "Net-(IC1-RG5{slash}~{MCLR})") (class "Default")
      (node (ref "IC1") (pin "7") (pinfunction "RG5/~{MCLR}_7") (pintype "input"))
      (node (ref "ICSP") (pin "1") (pinfunction "1_1") (pintype "passive"))
    )
    (net (code "59") (name "Net-(IC1-RG6)") (class "Default")
      (node (ref "IC1") (pin "20") (pinfunction "RG6_20") (pintype "bidirectional"))
      (node (ref "U$5") (pin "6") (pinfunction "TX/RC4_6") (pintype "bidirectional"))
    )
    (net (code "60") (name "Net-(IC1-RG7)") (class "Default")
      (node (ref "IC1") (pin "19") (pinfunction "RG7_19") (pintype "bidirectional"))
      (node (ref "U$5") (pin "5") (pinfunction "PWM1/RX/RC5_5") (pintype "bidirectional"))
    )
    (net (code "61") (name "Net-(IC2-3V3OUT)") (class "Default")
      (node (ref "C6") (pin "1") (pinfunction "1_1") (pintype "passive"))
      (node (ref "IC2") (pin "10") (pinfunction "3V3OUT_10") (pintype "output"))
      (node (ref "IC2") (pin "11") (pinfunction "~{RESET}_11") (pintype "input"))
      (node (ref "IC2") (pin "3") (pinfunction "VCCIO_3") (pintype "power_in"))
    )
    (net (code "62") (name "Net-(IC2-USBDM)") (class "Default")
      (node (ref "IC2") (pin "9") (pinfunction "USBDM_9") (pintype "input"))
      (node (ref "R3") (pin "1") (pinfunction "1_1") (pintype "passive"))
    )
    (net (code "63") (name "Net-(IC2-USBDP)") (class "Default")
      (node (ref "IC2") (pin "8") (pinfunction "USBDP_8") (pintype "input"))
      (node (ref "R2") (pin "1") (pinfunction "1_1") (pintype "passive"))
    )
    (net (code "64") (name "Net-(IC2-VCC)") (class "Default")
      (node (ref "C10") (pin "1") (pinfunction "1_1") (pintype "passive"))
      (node (ref "C7") (pin "1") (pinfunction "1_1") (pintype "passive"))
      (node (ref "D1") (pin "A") (pinfunction "A_A") (pintype "passive"))
      (node (ref "IC2") (pin "12") (pinfunction "VCC_12") (pintype "power_in"))
      (node (ref "IC8") (pin "4") (pinfunction "VDD_4") (pintype "power_in"))
      (node (ref "PTC1") (pin "1") (pinfunction "1_1") (pintype "passive"))
      (node (ref "PTC2") (pin "2") (pinfunction "2_2") (pintype "passive"))
      (node (ref "R6") (pin "2") (pinfunction "2_2") (pintype "passive"))
      (node (ref "TR3") (pin "1") (pinfunction "G_1") (pintype "bidirectional"))
      (node (ref "TR4") (pin "1") (pinfunction "G_1") (pintype "bidirectional"))
    )
    (net (code "65") (name "Net-(IC2-~{RTS})") (class "Default")
      (node (ref "IC2") (pin "2") (pinfunction "~{RTS}_2") (pintype "output"))
      (node (ref "R10") (pin "2") (pinfunction "2_2") (pintype "passive"))
    )
    (net (code "66") (name "Net-(IC3-GPIO4)") (class "Default")
      (node (ref "IC3") (pin "22") (pinfunction "GPIO4_22") (pintype "bidirectional"))
      (node (ref "SJ1") (pin "1") (pinfunction "1_1") (pintype "passive"))
    )
    (net (code "67") (name "Net-(IC3-UART_RTS)") (class "Default")
      (node (ref "IC3") (pin "15") (pinfunction "UART_RTS_15") (pintype "bidirectional"))
      (node (ref "R7") (pin "2") (pinfunction "2_2") (pintype "passive"))
    )
    (net (code "68") (name "Net-(IC8-PROG)") (class "Default")
      (node (ref "IC8") (pin "5") (pinfunction "PROG_5") (pintype "input"))
      (node (ref "R4") (pin "2") (pinfunction "2_2") (pintype "passive"))
      (node (ref "R5") (pin "2") (pinfunction "2_2") (pintype "passive"))
    )
    (net (code "69") (name "Net-(IC10-EN)") (class "Default")
      (node (ref "IC10") (pin "3") (pinfunction "EN_3") (pintype "input"))
      (node (ref "IC9") (pin "1") (pinfunction "~{LVD}_1") (pintype "output"))
    )
    (net (code "70") (name "Net-(IC10-IN)") (class "Default")
      (node (ref "C2") (pin "1") (pinfunction "1_1") (pintype "passive"))
      (node (ref "D1") (pin "C") (pinfunction "C_C") (pintype "passive"))
      (node (ref "IC10") (pin "1") (pinfunction "IN_1") (pintype "power_in"))
      (node (ref "IC9") (pin "2") (pinfunction "VCC_2") (pintype "power_in"))
      (node (ref "PTC3") (pin "1") (pinfunction "1_1") (pintype "passive"))
      (node (ref "TR3") (pin "2") (pinfunction "S_2") (pintype "bidirectional"))
    )
    (net (code "71") (name "Net-(LED1-PadA)") (class "Default")
      (node (ref "LED1") (pin "A") (pinfunction "A_A") (pintype "passive"))
      (node (ref "R1") (pin "2") (pinfunction "2_2") (pintype "passive"))
    )
    (net (code "72") (name "Net-(LED2-PadC)") (class "Default")
      (node (ref "LED2") (pin "C") (pinfunction "C_C") (pintype "passive"))
      (node (ref "R14") (pin "2") (pinfunction "2_2") (pintype "passive"))
    )
    (net (code "73") (name "Net-(LED3-PadC)") (class "Default")
      (node (ref "LED3") (pin "C") (pinfunction "C_C") (pintype "passive"))
      (node (ref "R15") (pin "2") (pinfunction "2_2") (pintype "passive"))
    )
    (net (code "74") (name "Net-(LED4-PadC)") (class "Default")
      (node (ref "LED4") (pin "C") (pinfunction "C_C") (pintype "passive"))
      (node (ref "R16") (pin "2") (pinfunction "2_2") (pintype "passive"))
    )
    (net (code "75") (name "Net-(SW3-2)") (class "Default")
      (node (ref "R8") (pin "2") (pinfunction "2_2") (pintype "passive"))
      (node (ref "SW3") (pin "P$2") (pinfunction "2_P$2") (pintype "bidirectional"))
      (node (ref "SW3") (pin "P$3") (pinfunction "3_P$3") (pintype "bidirectional"))
      (node (ref "TR3") (pin "3") (pinfunction "D_3") (pintype "bidirectional"))
    )
    (net (code "76") (name "Net-(TR1-D)") (class "Default")
      (node (ref "R5") (pin "1") (pinfunction "1_1") (pintype "passive"))
      (node (ref "TR1") (pin "3") (pinfunction "D_3") (pintype "bidirectional"))
    )
    (net (code "77") (name "Net-(TR2-D)") (class "Default")
      (node (ref "R8") (pin "1") (pinfunction "1_1") (pintype "passive"))
      (node (ref "TR2") (pin "3") (pinfunction "D_3") (pintype "bidirectional"))
    )
    (net (code "78") (name "Net-(TR4-S)") (class "Default")
      (node (ref "C13") (pin "1") (pinfunction "1_1") (pintype "passive"))
      (node (ref "TR4") (pin "2") (pinfunction "S_2") (pintype "bidirectional"))
      (node (ref "U$5") (pin "1") (pinfunction "VDD_1") (pintype "power_in"))
      (node (ref "U$5") (pin "11") (pinfunction "VUSB3V3_11") (pintype "power_in"))
    )
    (net (code "79") (name "VDD") (class "Default")
      (node (ref "C1") (pin "2") (pinfunction "2_2") (pintype "passive"))
      (node (ref "C11") (pin "1") (pinfunction "1_1") (pintype "passive"))
      (node (ref "C4") (pin "2") (pinfunction "2_2") (pintype "passive"))
      (node (ref "C8") (pin "1") (pinfunction "1_1") (pintype "passive"))
      (node (ref "CN2") (pin "3") (pinfunction "3_3") (pintype "passive"))
      (node (ref "IC1") (pin "10") (pinfunction "VDD_10") (pintype "power_in"))
      (node (ref "IC1") (pin "38") (pinfunction "VDD_38") (pintype "power_in"))
      (node (ref "IC10") (pin "5") (pinfunction "OUT_5") (pintype "output"))
      (node (ref "IC3") (pin "11") (pinfunction "VDD_11") (pintype "bidirectional"))
      (node (ref "ICSP") (pin "2") (pinfunction "2_2") (pintype "passive"))
      (node (ref "TR4") (pin "3") (pinfunction "D_3") (pintype "bidirectional"))
    )
    (net (code "80") (name "unconnected-(CN1-4-PadP$4)") (class "Default")
      (node (ref "CN1") (pin "P$4") (pinfunction "4_P$4") (pintype "passive"))
    )
    (net (code "81") (name "unconnected-(CN3-4-PadP$4)") (class "Default")
      (node (ref "CN3") (pin "P$4") (pinfunction "4_P$4") (pintype "passive"))
    )
    (net (code "82") (name "unconnected-(IC1-RH0-Pad26)") (class "Default")
      (node (ref "IC1") (pin "26") (pinfunction "RH0_26") (pintype "bidirectional"))
    )
    (net (code "83") (name "unconnected-(IC2-CBUS2-Pad7)") (class "Default")
      (node (ref "IC2") (pin "7") (pinfunction "CBUS2_7") (pintype "bidirectional"))
    )
    (net (code "84") (name "unconnected-(IC3-AIO0-Pad30)") (class "Default")
      (node (ref "IC3") (pin "30") (pinfunction "AIO0_30") (pintype "bidirectional"))
    )
    (net (code "85") (name "unconnected-(IC3-AIO1-Pad35)") (class "Default")
      (node (ref "IC3") (pin "35") (pinfunction "AIO1_35") (pintype "bidirectional"))
    )
    (net (code "86") (name "unconnected-(IC3-GPIO2-Pad19)") (class "Default")
      (node (ref "IC3") (pin "19") (pinfunction "GPIO2_19") (pintype "bidirectional"))
    )
    (net (code "87") (name "unconnected-(IC3-GPIO3-Pad20)") (class "Default")
      (node (ref "IC3") (pin "20") (pinfunction "GPIO3_20") (pintype "bidirectional"))
    )
    (net (code "88") (name "unconnected-(IC3-GPIO7-Pad4)") (class "Default")
      (node (ref "IC3") (pin "4") (pinfunction "GPIO7_4") (pintype "bidirectional"))
    )
    (net (code "89") (name "unconnected-(IC3-GPIO8-Pad31)") (class "Default")
      (node (ref "IC3") (pin "31") (pinfunction "GPIO8_31") (pintype "bidirectional"))
    )
    (net (code "90") (name "unconnected-(IC3-GPIO9-Pad32)") (class "Default")
      (node (ref "IC3") (pin "32") (pinfunction "GPIO9_32") (pintype "bidirectional"))
    )
    (net (code "91") (name "unconnected-(IC3-GPIO10-Pad33)") (class "Default")
      (node (ref "IC3") (pin "33") (pinfunction "GPIO10_33") (pintype "bidirectional"))
    )
    (net (code "92") (name "unconnected-(IC3-GPIO11-Pad34)") (class "Default")
      (node (ref "IC3") (pin "34") (pinfunction "GPIO11_34") (pintype "bidirectional"))
    )
    (net (code "93") (name "unconnected-(IC3-PCM_CLK-Pad7)") (class "Default")
      (node (ref "IC3") (pin "7") (pinfunction "PCM_CLK_7") (pintype "bidirectional"))
    )
    (net (code "94") (name "unconnected-(IC3-PCM_IN-Pad9)") (class "Default")
      (node (ref "IC3") (pin "9") (pinfunction "PCM_IN_9") (pintype "bidirectional"))
    )
    (net (code "95") (name "unconnected-(IC3-PCM_OUT-Pad10)") (class "Default")
      (node (ref "IC3") (pin "10") (pinfunction "PCM_OUT_10") (pintype "bidirectional"))
    )
    (net (code "96") (name "unconnected-(IC3-PCM_SYNC-Pad8)") (class "Default")
      (node (ref "IC3") (pin "8") (pinfunction "PCM_SYNC_8") (pintype "bidirectional"))
    )
    (net (code "97") (name "unconnected-(IC3-SPI_CLOCK-Pad6)") (class "Default")
      (node (ref "IC3") (pin "6") (pinfunction "SPI_CLOCK_6") (pintype "bidirectional"))
    )
    (net (code "98") (name "unconnected-(IC3-SPI_CSB-Pad23)") (class "Default")
      (node (ref "IC3") (pin "23") (pinfunction "SPI_CSB_23") (pintype "bidirectional"))
    )
    (net (code "99") (name "unconnected-(IC3-SPI_MISO-Pad24)") (class "Default")
      (node (ref "IC3") (pin "24") (pinfunction "SPI_MISO_24") (pintype "bidirectional"))
    )
    (net (code "100") (name "unconnected-(IC3-SPI_MOSI-Pad2)") (class "Default")
      (node (ref "IC3") (pin "2") (pinfunction "SPI_MOSI_2") (pintype "bidirectional"))
    )
    (net (code "101") (name "unconnected-(IC3-USB_D+-Pad17)") (class "Default")
      (node (ref "IC3") (pin "17") (pinfunction "USB_D+_17") (pintype "bidirectional"))
    )
    (net (code "102") (name "unconnected-(IC3-USB_D--Pad18)") (class "Default")
      (node (ref "IC3") (pin "18") (pinfunction "USB_D-_18") (pintype "bidirectional"))
    )
    (net (code "103") (name "unconnected-(ICSP1-Pad1)") (class "Default")
      (node (ref "ICSP1") (pin "1") (pinfunction "1_1") (pintype "passive"))
    )
    (net (code "104") (name "unconnected-(ICSP1-Pad2)") (class "Default")
      (node (ref "ICSP1") (pin "2") (pinfunction "2_2") (pintype "passive"))
    )
    (net (code "105") (name "unconnected-(ICSP1-Pad3)") (class "Default")
      (node (ref "ICSP1") (pin "3") (pinfunction "3_3") (pintype "passive"))
    )
    (net (code "106") (name "unconnected-(ICSP1-Pad4)") (class "Default")
      (node (ref "ICSP1") (pin "4") (pinfunction "4_4") (pintype "passive"))
    )
    (net (code "107") (name "unconnected-(ICSP1-Pad5)") (class "Default")
      (node (ref "ICSP1") (pin "5") (pinfunction "5_5") (pintype "passive"))
    )
    (net (code "108") (name "unconnected-(LED2-PadA)") (class "Default")
      (node (ref "LED2") (pin "A") (pinfunction "A_A") (pintype "passive"))
    )
    (net (code "109") (name "unconnected-(LED3-PadA)") (class "Default")
      (node (ref "LED3") (pin "A") (pinfunction "A_A") (pintype "passive"))
    )
    (net (code "110") (name "unconnected-(LED4-PadA)") (class "Default")
      (node (ref "LED4") (pin "A") (pinfunction "A_A") (pintype "passive"))
    )
    (net (code "111") (name "unconnected-(U$5-INT{slash}SDA{slash}SDI{slash}PGC{slash}RC1-Pad9)") (class "Default")
      (node (ref "U$5") (pin "9") (pinfunction "INT/SDA/SDI/PGC/RC1_9") (pintype "bidirectional"))
    )
    (net (code "112") (name "unconnected-(U$5-PWM2{slash}OSC1{slash}RA5-Pad2)") (class "Default")
      (node (ref "U$5") (pin "2") (pinfunction "PWM2/OSC1/RA5_2") (pintype "input"))
    )
    (net (code "113") (name "unconnected-(U$5-SCL{slash}SCK{slash}PGD{slash}RC0-Pad10)") (class "Default")
      (node (ref "U$5") (pin "10") (pinfunction "SCL/SCK/PGD/RC0_10") (pintype "bidirectional"))
    )
    (net (code "114") (name "unconnected-(U$5-SDO{slash}OSC2{slash}RA4-Pad3)") (class "Default")
      (node (ref "U$5") (pin "3") (pinfunction "SDO/OSC2/RA4_3") (pintype "bidirectional"))
    )
    (net (code "115") (name "unconnected-(U$5-SDO{slash}RC2-Pad8)") (class "Default")
      (node (ref "U$5") (pin "8") (pinfunction "SDO/RC2_8") (pintype "bidirectional"))
    )
    (net (code "116") (name "unconnected-(U$5-~{SS}{slash}VPP{slash}~{MCLR}{slash}RA3-Pad4)") (class "Default")
      (node (ref "U$5") (pin "4") (pinfunction "~{SS}/VPP/~{MCLR}/RA3_4") (pintype "bidirectional"))
    )
  )
)
